# power.net
KiCad netlist of a schematic drawn in Altium Designer
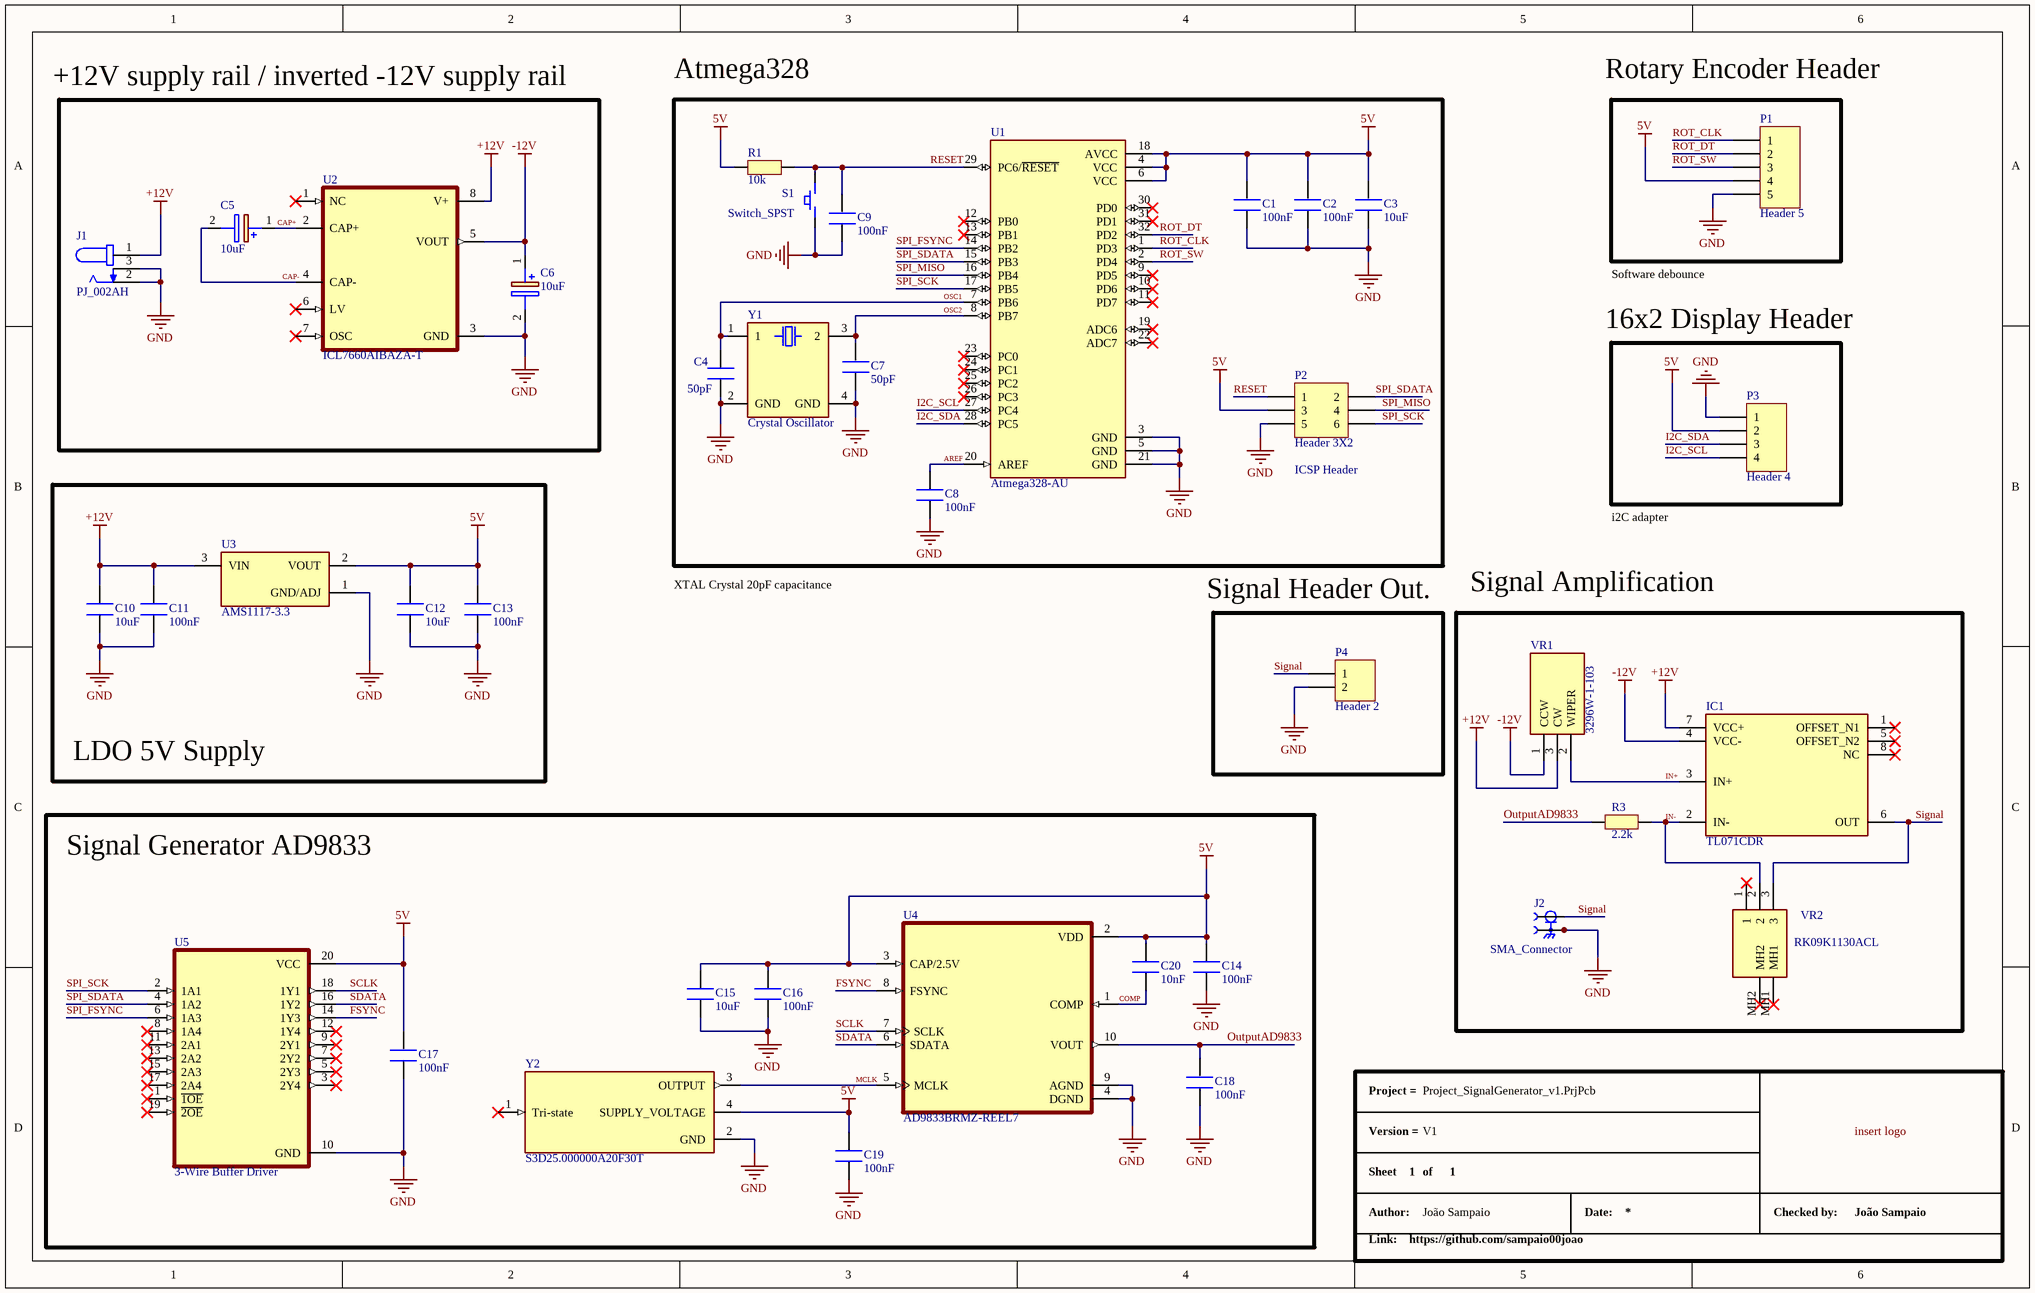
[diagram p0: power.SchDoc]

(export (version "E")
  (design (tool "Eeschema 10.0.6"))
  (components
    (comp (ref "C1")
      (value "100nF")
      (footprint "CAP_0603")
      (description "Capacitor SMD 0603 Generic")
      (libsource (lib "GenericCompLib") (part "Cap_0603"))
    )
    (comp (ref "C2")
      (value "100nF")
      (footprint "CAP_0603")
      (description "Capacitor SMD 0603 Generic")
      (libsource (lib "GenericCompLib") (part "Cap_0603"))
    )
    (comp (ref "C3")
      (value "10uF")
      (footprint "CAP_0603")
      (description "Capacitor SMD 0603 Generic")
      (libsource (lib "GenericCompLib") (part "Cap_0603"))
    )
    (comp (ref "C4")
      (value "50pF")
      (footprint "CAP_0603")
      (description "Capacitor SMD 0603 Generic")
      (libsource (lib "GenericCompLib") (part "Cap_0603"))
    )
    (comp (ref "C5")
      (value "10uF")
      (footprint "SamacSys:EEE1AA220WR")
      (description "Capacitor Polarised")
      (fields
        (field (name "MANUFACTURER_PART_NUMBER") "EEE-1CA100SR")
        (field (name "MOUSER PART NUMBER") "667-EEE-1CA100SR")
      )
      (libsource (lib "SamacSys") (part "EEE-1CA100SR"))
    )
    (comp (ref "C6")
      (value "10uF")
      (footprint "SamacSys:EEE1AA220WR")
      (description "Capacitor Polarised")
      (fields
        (field (name "MANUFACTURER_PART_NUMBER") "EEE-1CA100SR")
        (field (name "MOUSER PART NUMBER") "667-EEE-1CA100SR")
      )
      (libsource (lib "") (part "EEE-1CA100SR_1"))
    )
    (comp (ref "C7")
      (value "50pF")
      (footprint "CAP_0603")
      (description "Capacitor SMD 0603 Generic")
      (libsource (lib "GenericCompLib") (part "Cap_0603"))
    )
    (comp (ref "C8")
      (value "100nF")
      (footprint "CAP_0603")
      (description "Capacitor SMD 0603 Generic")
      (libsource (lib "GenericCompLib") (part "Cap_0603"))
    )
    (comp (ref "C9")
      (value "100nF")
      (footprint "CAP_0603")
      (description "Capacitor SMD 0603 Generic")
      (libsource (lib "GenericCompLib") (part "Cap_0603"))
    )
    (comp (ref "C10")
      (value "10uF")
      (footprint "CAP_0603")
      (description "Capacitor SMD 0603 Generic")
      (libsource (lib "GenericCompLib") (part "Cap_0603"))
    )
    (comp (ref "C11")
      (value "100nF")
      (footprint "CAP_0603")
      (description "Capacitor SMD 0603 Generic")
      (libsource (lib "GenericCompLib") (part "Cap_0603"))
    )
    (comp (ref "C12")
      (value "10uF")
      (footprint "CAP_0603")
      (description "Capacitor SMD 0603 Generic")
      (libsource (lib "GenericCompLib") (part "Cap_0603"))
    )
    (comp (ref "C13")
      (value "100nF")
      (footprint "CAP_0603")
      (description "Capacitor SMD 0603 Generic")
      (libsource (lib "GenericCompLib") (part "Cap_0603"))
    )
    (comp (ref "C14")
      (value "100nF")
      (footprint "CAP_0603")
      (description "Capacitor SMD 0603 Generic")
      (libsource (lib "GenericCompLib") (part "Cap_0603"))
    )
    (comp (ref "C15")
      (value "10uF")
      (footprint "CAP_0603")
      (description "Capacitor SMD 0603 Generic")
      (libsource (lib "GenericCompLib") (part "Cap_0603"))
    )
    (comp (ref "C16")
      (value "100nF")
      (footprint "CAP_0603")
      (description "Capacitor SMD 0603 Generic")
      (libsource (lib "GenericCompLib") (part "Cap_0603"))
    )
    (comp (ref "C17")
      (value "100nF")
      (footprint "CAP_0603")
      (description "Capacitor SMD 0603 Generic")
      (libsource (lib "GenericCompLib") (part "Cap_0603"))
    )
    (comp (ref "C18")
      (value "100nF")
      (footprint "CAP_0603")
      (description "Capacitor SMD 0603 Generic")
      (libsource (lib "GenericCompLib") (part "Cap_0603"))
    )
    (comp (ref "C19")
      (value "100nF")
      (footprint "CAP_0603")
      (description "Capacitor SMD 0603 Generic")
      (libsource (lib "GenericCompLib") (part "Cap_0603"))
    )
    (comp (ref "C20")
      (value "10nF")
      (footprint "CAP_0603")
      (description "Capacitor SMD 0603 Generic")
      (libsource (lib "GenericCompLib") (part "Cap_0603"))
    )
    (comp (ref "IC1")
      (value "TL071CDR")
      (footprint "SamacSys:SOIC127P600X175-8N")
      (description "Integrated Circuit")
      (fields (field (name "MOUSER PART NUMBER") "595-TL071CDR"))
      (libsource (lib "SamacSys") (part "TL071CDR"))
    )
    (comp (ref "J1")
      (value "PJ_002AH")
      (footprint "DCJack_3pins")
      (libsource (lib "ConnLib") (part "DCJack_3pins"))
    )
    (comp (ref "J2")
      (value "SMA_Connector")
      (footprint "SMA_Connector")
      (description "RF Coaxial Straight SMA Connector")
      (libsource (lib "ConnLib") (part "SMA_Connector"))
    )
    (comp (ref "P1")
      (value "Header 5")
      (footprint "HDR1X5")
      (description "Header, 5-Pin")
      (fields (field (name "PUBLISHER") "Altium Limited"))
      (libsource (lib "Miscellaneous Connectors") (part "Header 5"))
    )
    (comp (ref "P2")
      (value "Header 3X2")
      (footprint "HDR2X3")
      (description "Header, 3-Pin, Dual row")
      (fields (field (name "PUBLISHER") "Altium Limited"))
      (libsource (lib "Miscellaneous Connectors") (part "Header 3X2"))
    )
    (comp (ref "P3")
      (value "Header 4")
      (footprint "HDR1X4")
      (description "Header, 4-Pin")
      (fields (field (name "PUBLISHER") "Altium Limited"))
      (libsource (lib "Miscellaneous Connectors") (part "Header 4"))
    )
    (comp (ref "P4")
      (value "Header 2")
      (footprint "HDR1X2")
      (description "Header, 2-Pin")
      (fields (field (name "PUBLISHER") "Altium Limited"))
      (libsource (lib "Miscellaneous Connectors") (part "Header 2"))
    )
    (comp (ref "R1")
      (value "10k")
      (footprint "RES_0603")
      (description "Resistor SMD 0603 Generic")
      (libsource (lib "GenericCompLib") (part "Res_0603"))
    )
    (comp (ref "R3")
      (value "2.2k")
      (footprint "RES_0603")
      (description "Resistor SMD 0603 Generic")
      (libsource (lib "GenericCompLib") (part "Res_0603"))
    )
    (comp (ref "S1")
      (value "Switch_SPST")
      (footprint "SPST-NO_Switch")
      (description "Switch_SPST 2 pins")
      (libsource (lib "GenericCompLib") (part "Switch_SPST"))
    )
    (comp (ref "U1")
      (value "Atmega328-AU")
      (footprint "ATMEGA328-AU")
      (description "AVR AVR® ATmega Microcontroller IC 8-Bit 20MHz 32KB (16K x 16) FLASH 32-TQFP (7x7)")
      (libsource (lib "ICLib") (part "Atmega328-AU"))
    )
    (comp (ref "U2")
      (value "ICL7660AIBAZA-T")
      (footprint "ICL7660AIBAZA-T")
      (libsource (lib "PowerSupplyICLib") (part "ICL7660A"))
    )
    (comp (ref "U3")
      (value "AMS1117-3.3")
      (footprint "SOT229P700X180-4N")
      (description "Sot223/Pkg 1-Amp 3.3-Volt Low Drop Out Voltage Regulatator")
      (libsource (lib "PowerSupplyICLib") (part "AMS1117-3.3"))
    )
    (comp (ref "U4")
      (value "AD9833BRMZ-REEL7")
      (footprint "AD9833BRMZ-REEL7")
      (description "Direct Digital Synthesis IC 10 b 25 MHz 28 b Tuning 10-MSOP")
      (libsource (lib "ICLib") (part "AD9833BRMZ-REEL7"))
    )
    (comp (ref "U5")
      (value "3-Wire Buffer Driver")
      (footprint "SOP65P640X120-20N")
      (description "Octal Buffers And Line Drivers With 3-State Outputs 20-TSSOP -40 to 85")
      (libsource (lib "ICLib") (part "SN74HCT244PWR"))
    )
    (comp (ref "VR1")
      (value "3296W-1-103")
      (footprint "SamacSys:3296W1103")
      (description "Variable Resistor")
      (libsource (lib "SamacSys") (part "3296W-1-103"))
    )
    (comp (ref "VR2")
      (value "RK09K1130ACL")
      (footprint "SamacSys:RK09K1130ACL")
      (description "Variable Resistor")
      (fields (field (name "MOUSER PART NUMBER") "688-RK09K1130ACL"))
      (libsource (lib "SamacSys") (part "RK09K1130ACL"))
    )
    (comp (ref "Y1")
      (value "Crystal Oscillator")
      (footprint "4pinOscillator")
      (libsource (lib "OscLib") (part "4pinOscillator"))
    )
    (comp (ref "Y2")
      (value "S3D25.000000A20F30T")
      (footprint "OSC_ECS-327TXO-30-TR")
      (description "Oscillator TCXO 0.032768MHz Â±1.5ppm (Tol) Â±5ppm (Stability) 15pF CMOS 60% 3V 4-Pin CSMD T/R")
      (libsource (lib "OscLib") (part "ECS-327TXO-30-TR"))
    )
  )
  (nets
    (net (code "1") (name "+12V") (class "Default")
      (node (ref "C10") (pin "2") (pinfunction "2_2") (pintype "passive"))
      (node (ref "C11") (pin "2") (pinfunction "2_2") (pintype "passive"))
      (node (ref "IC1") (pin "7") (pinfunction "VCC+_7") (pintype "passive"))
      (node (ref "J1") (pin "1") (pinfunction "1_1") (pintype "passive"))
      (node (ref "U2") (pin "8") (pinfunction "V+_8") (pintype "power_in"))
      (node (ref "U3") (pin "3") (pinfunction "VIN_3") (pintype "power_in"))
      (node (ref "VR1") (pin "3") (pinfunction "CW_3") (pintype "passive"))
    )
    (net (code "2") (name "-12V") (class "Default")
      (node (ref "C6") (pin "1") (pinfunction "+_1") (pintype "passive"))
      (node (ref "IC1") (pin "4") (pinfunction "VCC-_4") (pintype "passive"))
      (node (ref "U2") (pin "5") (pinfunction "VOUT_5") (pintype "output"))
      (node (ref "VR1") (pin "1") (pinfunction "CCW_1") (pintype "passive"))
    )
    (net (code "3") (name "/AREF") (class "Default")
      (node (ref "C8") (pin "2") (pinfunction "2_2") (pintype "passive"))
      (node (ref "U1") (pin "20") (pinfunction "AREF_20") (pintype "input"))
    )
    (net (code "4") (name "/CAP+") (class "Default")
      (node (ref "C5") (pin "1") (pinfunction "+_1") (pintype "passive"))
      (node (ref "U2") (pin "2") (pinfunction "CAP+_2") (pintype "passive"))
    )
    (net (code "5") (name "/CAP-") (class "Default")
      (node (ref "C5") (pin "2") (pinfunction "-_2") (pintype "passive"))
      (node (ref "U2") (pin "4") (pinfunction "CAP-_4") (pintype "passive"))
    )
    (net (code "6") (name "/COMP") (class "Default")
      (node (ref "C20") (pin "1") (pinfunction "1_1") (pintype "passive"))
      (node (ref "U4") (pin "1") (pinfunction "COMP_1") (pintype "input"))
    )
    (net (code "7") (name "/FSYNC") (class "Default")
      (node (ref "U4") (pin "8") (pinfunction "FSYNC_8") (pintype "input"))
      (node (ref "U5") (pin "14") (pinfunction "1Y3_14") (pintype "output"))
    )
    (net (code "8") (name "/I2C_SCL") (class "Default")
      (node (ref "P3") (pin "4") (pinfunction "4_4") (pintype "passive"))
      (node (ref "U1") (pin "27") (pinfunction "PC4_27") (pintype "bidirectional"))
    )
    (net (code "9") (name "/I2C_SDA") (class "Default")
      (node (ref "P3") (pin "3") (pinfunction "3_3") (pintype "passive"))
      (node (ref "U1") (pin "28") (pinfunction "PC5_28") (pintype "bidirectional"))
    )
    (net (code "10") (name "/IN+") (class "Default")
      (node (ref "IC1") (pin "3") (pinfunction "IN+_3") (pintype "passive"))
      (node (ref "VR1") (pin "2") (pinfunction "WIPER_2") (pintype "passive"))
    )
    (net (code "11") (name "/IN-") (class "Default")
      (node (ref "IC1") (pin "2") (pinfunction "IN-_2") (pintype "passive"))
      (node (ref "R3") (pin "1") (pinfunction "1_1") (pintype "passive"))
      (node (ref "VR2") (pin "2") (pinfunction "2_2") (pintype "passive"))
    )
    (net (code "12") (name "/MCLK") (class "Default")
      (node (ref "U4") (pin "5") (pinfunction "MCLK_5") (pintype "input"))
      (node (ref "Y2") (pin "3") (pinfunction "OUTPUT_3") (pintype "output"))
    )
    (net (code "13") (name "/OSC1") (class "Default")
      (node (ref "C4") (pin "2") (pinfunction "2_2") (pintype "passive"))
      (node (ref "U1") (pin "7") (pinfunction "PB6_7") (pintype "bidirectional"))
      (node (ref "Y1") (pin "1") (pinfunction "1_1") (pintype "passive"))
    )
    (net (code "14") (name "/OSC2") (class "Default")
      (node (ref "C7") (pin "2") (pinfunction "2_2") (pintype "passive"))
      (node (ref "U1") (pin "8") (pinfunction "PB7_8") (pintype "bidirectional"))
      (node (ref "Y1") (pin "3") (pinfunction "2_3") (pintype "passive"))
    )
    (net (code "15") (name "/OutputAD9833") (class "Default")
      (node (ref "C18") (pin "2") (pinfunction "2_2") (pintype "passive"))
      (node (ref "R3") (pin "2") (pinfunction "2_2") (pintype "passive"))
      (node (ref "U4") (pin "10") (pinfunction "VOUT_10") (pintype "output"))
    )
    (net (code "16") (name "/RESET") (class "Default")
      (node (ref "C9") (pin "2") (pinfunction "2_2") (pintype "passive"))
      (node (ref "P2") (pin "1") (pinfunction "1_1") (pintype "passive"))
      (node (ref "R1") (pin "1") (pinfunction "1_1") (pintype "passive"))
      (node (ref "S1") (pin "2") (pinfunction "0_2") (pintype "passive"))
      (node (ref "U1") (pin "29") (pinfunction "PC6/~{RESET}_29") (pintype "bidirectional"))
    )
    (net (code "17") (name "/ROT_CLK") (class "Default")
      (node (ref "P1") (pin "1") (pinfunction "1_1") (pintype "passive"))
      (node (ref "U1") (pin "1") (pinfunction "PD3_1") (pintype "bidirectional"))
    )
    (net (code "18") (name "/ROT_DT") (class "Default")
      (node (ref "P1") (pin "2") (pinfunction "2_2") (pintype "passive"))
      (node (ref "U1") (pin "32") (pinfunction "PD2_32") (pintype "bidirectional"))
    )
    (net (code "19") (name "/ROT_SW") (class "Default")
      (node (ref "P1") (pin "3") (pinfunction "3_3") (pintype "passive"))
      (node (ref "U1") (pin "2") (pinfunction "PD4_2") (pintype "bidirectional"))
    )
    (net (code "20") (name "/SCLK") (class "Default")
      (node (ref "U4") (pin "7") (pinfunction "SCLK_7") (pintype "input"))
      (node (ref "U5") (pin "18") (pinfunction "1Y1_18") (pintype "output"))
    )
    (net (code "21") (name "/SDATA") (class "Default")
      (node (ref "U4") (pin "6") (pinfunction "SDATA_6") (pintype "input"))
      (node (ref "U5") (pin "16") (pinfunction "1Y2_16") (pintype "output"))
    )
    (net (code "22") (name "/SPI_FSYNC") (class "Default")
      (node (ref "U1") (pin "14") (pinfunction "PB2_14") (pintype "bidirectional"))
      (node (ref "U5") (pin "6") (pinfunction "1A3_6") (pintype "input"))
    )
    (net (code "23") (name "/SPI_MISO") (class "Default")
      (node (ref "P2") (pin "4") (pinfunction "4_4") (pintype "passive"))
      (node (ref "U1") (pin "16") (pinfunction "PB4_16") (pintype "bidirectional"))
    )
    (net (code "24") (name "/SPI_SCK") (class "Default")
      (node (ref "P2") (pin "6") (pinfunction "6_6") (pintype "passive"))
      (node (ref "U1") (pin "17") (pinfunction "PB5_17") (pintype "bidirectional"))
      (node (ref "U5") (pin "2") (pinfunction "1A1_2") (pintype "input"))
    )
    (net (code "25") (name "/SPI_SDATA") (class "Default")
      (node (ref "P2") (pin "2") (pinfunction "2_2") (pintype "passive"))
      (node (ref "U1") (pin "15") (pinfunction "PB3_15") (pintype "bidirectional"))
      (node (ref "U5") (pin "4") (pinfunction "1A2_4") (pintype "input"))
    )
    (net (code "26") (name "/Signal") (class "Default")
      (node (ref "IC1") (pin "6") (pinfunction "OUT_6") (pintype "passive"))
      (node (ref "J2") (pin "1") (pinfunction "1_1") (pintype "passive"))
      (node (ref "P4") (pin "1") (pinfunction "1_1") (pintype "passive"))
      (node (ref "VR2") (pin "3") (pinfunction "3_3") (pintype "passive"))
    )
    (net (code "28") (name "5V") (class "Default")
      (node (ref "C1") (pin "2") (pinfunction "2_2") (pintype "passive"))
      (node (ref "C12") (pin "2") (pinfunction "2_2") (pintype "passive"))
      (node (ref "C13") (pin "2") (pinfunction "2_2") (pintype "passive"))
      (node (ref "C14") (pin "2") (pinfunction "2_2") (pintype "passive"))
      (node (ref "C15") (pin "2") (pinfunction "2_2") (pintype "passive"))
      (node (ref "C16") (pin "2") (pinfunction "2_2") (pintype "passive"))
      (node (ref "C17") (pin "2") (pinfunction "2_2") (pintype "passive"))
      (node (ref "C19") (pin "2") (pinfunction "2_2") (pintype "passive"))
      (node (ref "C2") (pin "2") (pinfunction "2_2") (pintype "passive"))
      (node (ref "C20") (pin "2") (pinfunction "2_2") (pintype "passive"))
      (node (ref "C3") (pin "2") (pinfunction "2_2") (pintype "passive"))
      (node (ref "P1") (pin "4") (pinfunction "4_4") (pintype "passive"))
      (node (ref "P2") (pin "3") (pinfunction "3_3") (pintype "passive"))
      (node (ref "P3") (pin "2") (pinfunction "2_2") (pintype "passive"))
      (node (ref "R1") (pin "2") (pinfunction "2_2") (pintype "passive"))
      (node (ref "U1") (pin "18") (pinfunction "AVCC_18") (pintype "power_in"))
      (node (ref "U1") (pin "4") (pinfunction "VCC_4") (pintype "power_in"))
      (node (ref "U1") (pin "6") (pinfunction "VCC_6") (pintype "power_in"))
      (node (ref "U3") (pin "2") (pinfunction "VOUT_2") (pintype "power_in"))
      (node (ref "U4") (pin "2") (pinfunction "VDD_2") (pintype "power_in"))
      (node (ref "U4") (pin "3") (pinfunction "CAP/2.5V_3") (pintype "input"))
      (node (ref "U5") (pin "20") (pinfunction "VCC_20") (pintype "power_in"))
      (node (ref "Y2") (pin "4") (pinfunction "SUPPLY_VOLTAGE_4") (pintype "power_in"))
    )
    (net (code "29") (name "GND") (class "Default")
      (node (ref "C1") (pin "1") (pinfunction "1_1") (pintype "passive"))
      (node (ref "C10") (pin "1") (pinfunction "1_1") (pintype "passive"))
      (node (ref "C11") (pin "1") (pinfunction "1_1") (pintype "passive"))
      (node (ref "C12") (pin "1") (pinfunction "1_1") (pintype "passive"))
      (node (ref "C13") (pin "1") (pinfunction "1_1") (pintype "passive"))
      (node (ref "C14") (pin "1") (pinfunction "1_1") (pintype "passive"))
      (node (ref "C15") (pin "1") (pinfunction "1_1") (pintype "passive"))
      (node (ref "C16") (pin "1") (pinfunction "1_1") (pintype "passive"))
      (node (ref "C17") (pin "1") (pinfunction "1_1") (pintype "passive"))
      (node (ref "C18") (pin "1") (pinfunction "1_1") (pintype "passive"))
      (node (ref "C19") (pin "1") (pinfunction "1_1") (pintype "passive"))
      (node (ref "C2") (pin "1") (pinfunction "1_1") (pintype "passive"))
      (node (ref "C3") (pin "1") (pinfunction "1_1") (pintype "passive"))
      (node (ref "C4") (pin "1") (pinfunction "1_1") (pintype "passive"))
      (node (ref "C6") (pin "2") (pinfunction "-_2") (pintype "passive"))
      (node (ref "C7") (pin "1") (pinfunction "1_1") (pintype "passive"))
      (node (ref "C8") (pin "1") (pinfunction "1_1") (pintype "passive"))
      (node (ref "C9") (pin "1") (pinfunction "1_1") (pintype "passive"))
      (node (ref "J1") (pin "2") (pinfunction "2_2") (pintype "passive"))
      (node (ref "J1") (pin "3") (pinfunction "3_3") (pintype "passive"))
      (node (ref "J2") (pin "G1") (pinfunction "2_G1") (pintype "passive"))
      (node (ref "J2") (pin "G2") (pinfunction "2_G2") (pintype "passive"))
      (node (ref "J2") (pin "G3") (pinfunction "2_G3") (pintype "passive"))
      (node (ref "J2") (pin "G4") (pinfunction "2_G4") (pintype "passive"))
      (node (ref "P1") (pin "5") (pinfunction "5_5") (pintype "passive"))
      (node (ref "P2") (pin "5") (pinfunction "5_5") (pintype "passive"))
      (node (ref "P3") (pin "1") (pinfunction "1_1") (pintype "passive"))
      (node (ref "P4") (pin "2") (pinfunction "2_2") (pintype "passive"))
      (node (ref "S1") (pin "1") (pinfunction "0_1") (pintype "passive"))
      (node (ref "U1") (pin "21") (pinfunction "GND_21") (pintype "power_in"))
      (node (ref "U1") (pin "3") (pinfunction "GND_3") (pintype "power_in"))
      (node (ref "U1") (pin "5") (pinfunction "GND_5") (pintype "power_in"))
      (node (ref "U2") (pin "3") (pinfunction "GND_3") (pintype "passive"))
      (node (ref "U3") (pin "1") (pinfunction "GND/ADJ_1") (pintype "power_in"))
      (node (ref "U4") (pin "4") (pinfunction "DGND_4") (pintype "power_in"))
      (node (ref "U4") (pin "9") (pinfunction "AGND_9") (pintype "power_in"))
      (node (ref "U5") (pin "10") (pinfunction "GND_10") (pintype "power_in"))
      (node (ref "Y1") (pin "2") (pinfunction "GND_2") (pintype "power_in"))
      (node (ref "Y1") (pin "4") (pinfunction "GND_4") (pintype "power_in"))
      (node (ref "Y2") (pin "2") (pinfunction "GND_2") (pintype "power_in"))
    )
    (net (code "30") (name "unconnected-(IC1-NC-Pad8)") (class "Default")
      (node (ref "IC1") (pin "8") (pinfunction "NC_8") (pintype "passive+no_connect"))
    )
    (net (code "31") (name "unconnected-(IC1-OFFSET_N1-Pad1)") (class "Default")
      (node (ref "IC1") (pin "1") (pinfunction "OFFSET_N1_1") (pintype "passive+no_connect"))
    )
    (net (code "32") (name "unconnected-(IC1-OFFSET_N2-Pad5)") (class "Default")
      (node (ref "IC1") (pin "5") (pinfunction "OFFSET_N2_5") (pintype "passive+no_connect"))
    )
    (net (code "33") (name "unconnected-(U1-ADC6-Pad19)") (class "Default")
      (node (ref "U1") (pin "19") (pinfunction "ADC6_19") (pintype "bidirectional+no_connect"))
    )
    (net (code "34") (name "unconnected-(U1-ADC7-Pad22)") (class "Default")
      (node (ref "U1") (pin "22") (pinfunction "ADC7_22") (pintype "bidirectional+no_connect"))
    )
    (net (code "35") (name "unconnected-(U1-PB0-Pad12)") (class "Default")
      (node (ref "U1") (pin "12") (pinfunction "PB0_12") (pintype "bidirectional+no_connect"))
    )
    (net (code "36") (name "unconnected-(U1-PB1-Pad13)") (class "Default")
      (node (ref "U1") (pin "13") (pinfunction "PB1_13") (pintype "bidirectional+no_connect"))
    )
    (net (code "37") (name "unconnected-(U1-PC0-Pad23)") (class "Default")
      (node (ref "U1") (pin "23") (pinfunction "PC0_23") (pintype "bidirectional+no_connect"))
    )
    (net (code "38") (name "unconnected-(U1-PC1-Pad24)") (class "Default")
      (node (ref "U1") (pin "24") (pinfunction "PC1_24") (pintype "bidirectional+no_connect"))
    )
    (net (code "39") (name "unconnected-(U1-PC2-Pad25)") (class "Default")
      (node (ref "U1") (pin "25") (pinfunction "PC2_25") (pintype "bidirectional+no_connect"))
    )
    (net (code "40") (name "unconnected-(U1-PC3-Pad26)") (class "Default")
      (node (ref "U1") (pin "26") (pinfunction "PC3_26") (pintype "bidirectional+no_connect"))
    )
    (net (code "41") (name "unconnected-(U1-PD0-Pad30)") (class "Default")
      (node (ref "U1") (pin "30") (pinfunction "PD0_30") (pintype "bidirectional+no_connect"))
    )
    (net (code "42") (name "unconnected-(U1-PD1-Pad31)") (class "Default")
      (node (ref "U1") (pin "31") (pinfunction "PD1_31") (pintype "bidirectional+no_connect"))
    )
    (net (code "43") (name "unconnected-(U1-PD5-Pad9)") (class "Default")
      (node (ref "U1") (pin "9") (pinfunction "PD5_9") (pintype "bidirectional+no_connect"))
    )
    (net (code "44") (name "unconnected-(U1-PD6-Pad10)") (class "Default")
      (node (ref "U1") (pin "10") (pinfunction "PD6_10") (pintype "bidirectional+no_connect"))
    )
    (net (code "45") (name "unconnected-(U1-PD7-Pad11)") (class "Default")
      (node (ref "U1") (pin "11") (pinfunction "PD7_11") (pintype "bidirectional+no_connect"))
    )
    (net (code "46") (name "unconnected-(U2-LV-Pad6)") (class "Default")
      (node (ref "U2") (pin "6") (pinfunction "LV_6") (pintype "input+no_connect"))
    )
    (net (code "47") (name "unconnected-(U2-NC-Pad1)") (class "Default")
      (node (ref "U2") (pin "1") (pinfunction "NC_1") (pintype "input+no_connect"))
    )
    (net (code "48") (name "unconnected-(U2-OSC-Pad7)") (class "Default")
      (node (ref "U2") (pin "7") (pinfunction "OSC_7") (pintype "input+no_connect"))
    )
    (net (code "49") (name "unconnected-(U5-1A4-Pad8)") (class "Default")
      (node (ref "U5") (pin "8") (pinfunction "1A4_8") (pintype "input+no_connect"))
    )
    (net (code "50") (name "unconnected-(U5-1Y4-Pad12)") (class "Default")
      (node (ref "U5") (pin "12") (pinfunction "1Y4_12") (pintype "output+no_connect"))
    )
    (net (code "51") (name "unconnected-(U5-2A1-Pad11)") (class "Default")
      (node (ref "U5") (pin "11") (pinfunction "2A1_11") (pintype "input+no_connect"))
    )
    (net (code "52") (name "unconnected-(U5-2A2-Pad13)") (class "Default")
      (node (ref "U5") (pin "13") (pinfunction "2A2_13") (pintype "input+no_connect"))
    )
    (net (code "53") (name "unconnected-(U5-2A3-Pad15)") (class "Default")
      (node (ref "U5") (pin "15") (pinfunction "2A3_15") (pintype "input+no_connect"))
    )
    (net (code "54") (name "unconnected-(U5-2A4-Pad17)") (class "Default")
      (node (ref "U5") (pin "17") (pinfunction "2A4_17") (pintype "input+no_connect"))
    )
    (net (code "55") (name "unconnected-(U5-2Y1-Pad9)") (class "Default")
      (node (ref "U5") (pin "9") (pinfunction "2Y1_9") (pintype "output+no_connect"))
    )
    (net (code "56") (name "unconnected-(U5-2Y2-Pad7)") (class "Default")
      (node (ref "U5") (pin "7") (pinfunction "2Y2_7") (pintype "output+no_connect"))
    )
    (net (code "57") (name "unconnected-(U5-2Y3-Pad5)") (class "Default")
      (node (ref "U5") (pin "5") (pinfunction "2Y3_5") (pintype "output+no_connect"))
    )
    (net (code "58") (name "unconnected-(U5-2Y4-Pad3)") (class "Default")
      (node (ref "U5") (pin "3") (pinfunction "2Y4_3") (pintype "output+no_connect"))
    )
    (net (code "59") (name "unconnected-(U5-~{1OE}-Pad1)") (class "Default")
      (node (ref "U5") (pin "1") (pinfunction "~{1OE}_1") (pintype "input+no_connect"))
    )
    (net (code "60") (name "unconnected-(U5-~{2OE}-Pad19)") (class "Default")
      (node (ref "U5") (pin "19") (pinfunction "~{2OE}_19") (pintype "input+no_connect"))
    )
    (net (code "61") (name "unconnected-(VR2-Pad1)") (class "Default")
      (node (ref "VR2") (pin "1") (pinfunction "1_1") (pintype "passive+no_connect"))
    )
    (net (code "62") (name "unconnected-(VR2-PadMH1)") (class "Default")
      (node (ref "VR2") (pin "MH1") (pinfunction "MH1_MH1") (pintype "passive+no_connect"))
    )
    (net (code "63") (name "unconnected-(VR2-PadMH2)") (class "Default")
      (node (ref "VR2") (pin "MH2") (pinfunction "MH2_MH2") (pintype "passive+no_connect"))
    )
    (net (code "64") (name "unconnected-(Y2-Tri-state-Pad1)") (class "Default")
      (node (ref "Y2") (pin "1") (pinfunction "Tri-state_1") (pintype "input+no_connect"))
    )
  )
)
